# EasyEDApro.net
KiCad netlist of a schematic drawn in EasyEDA Pro
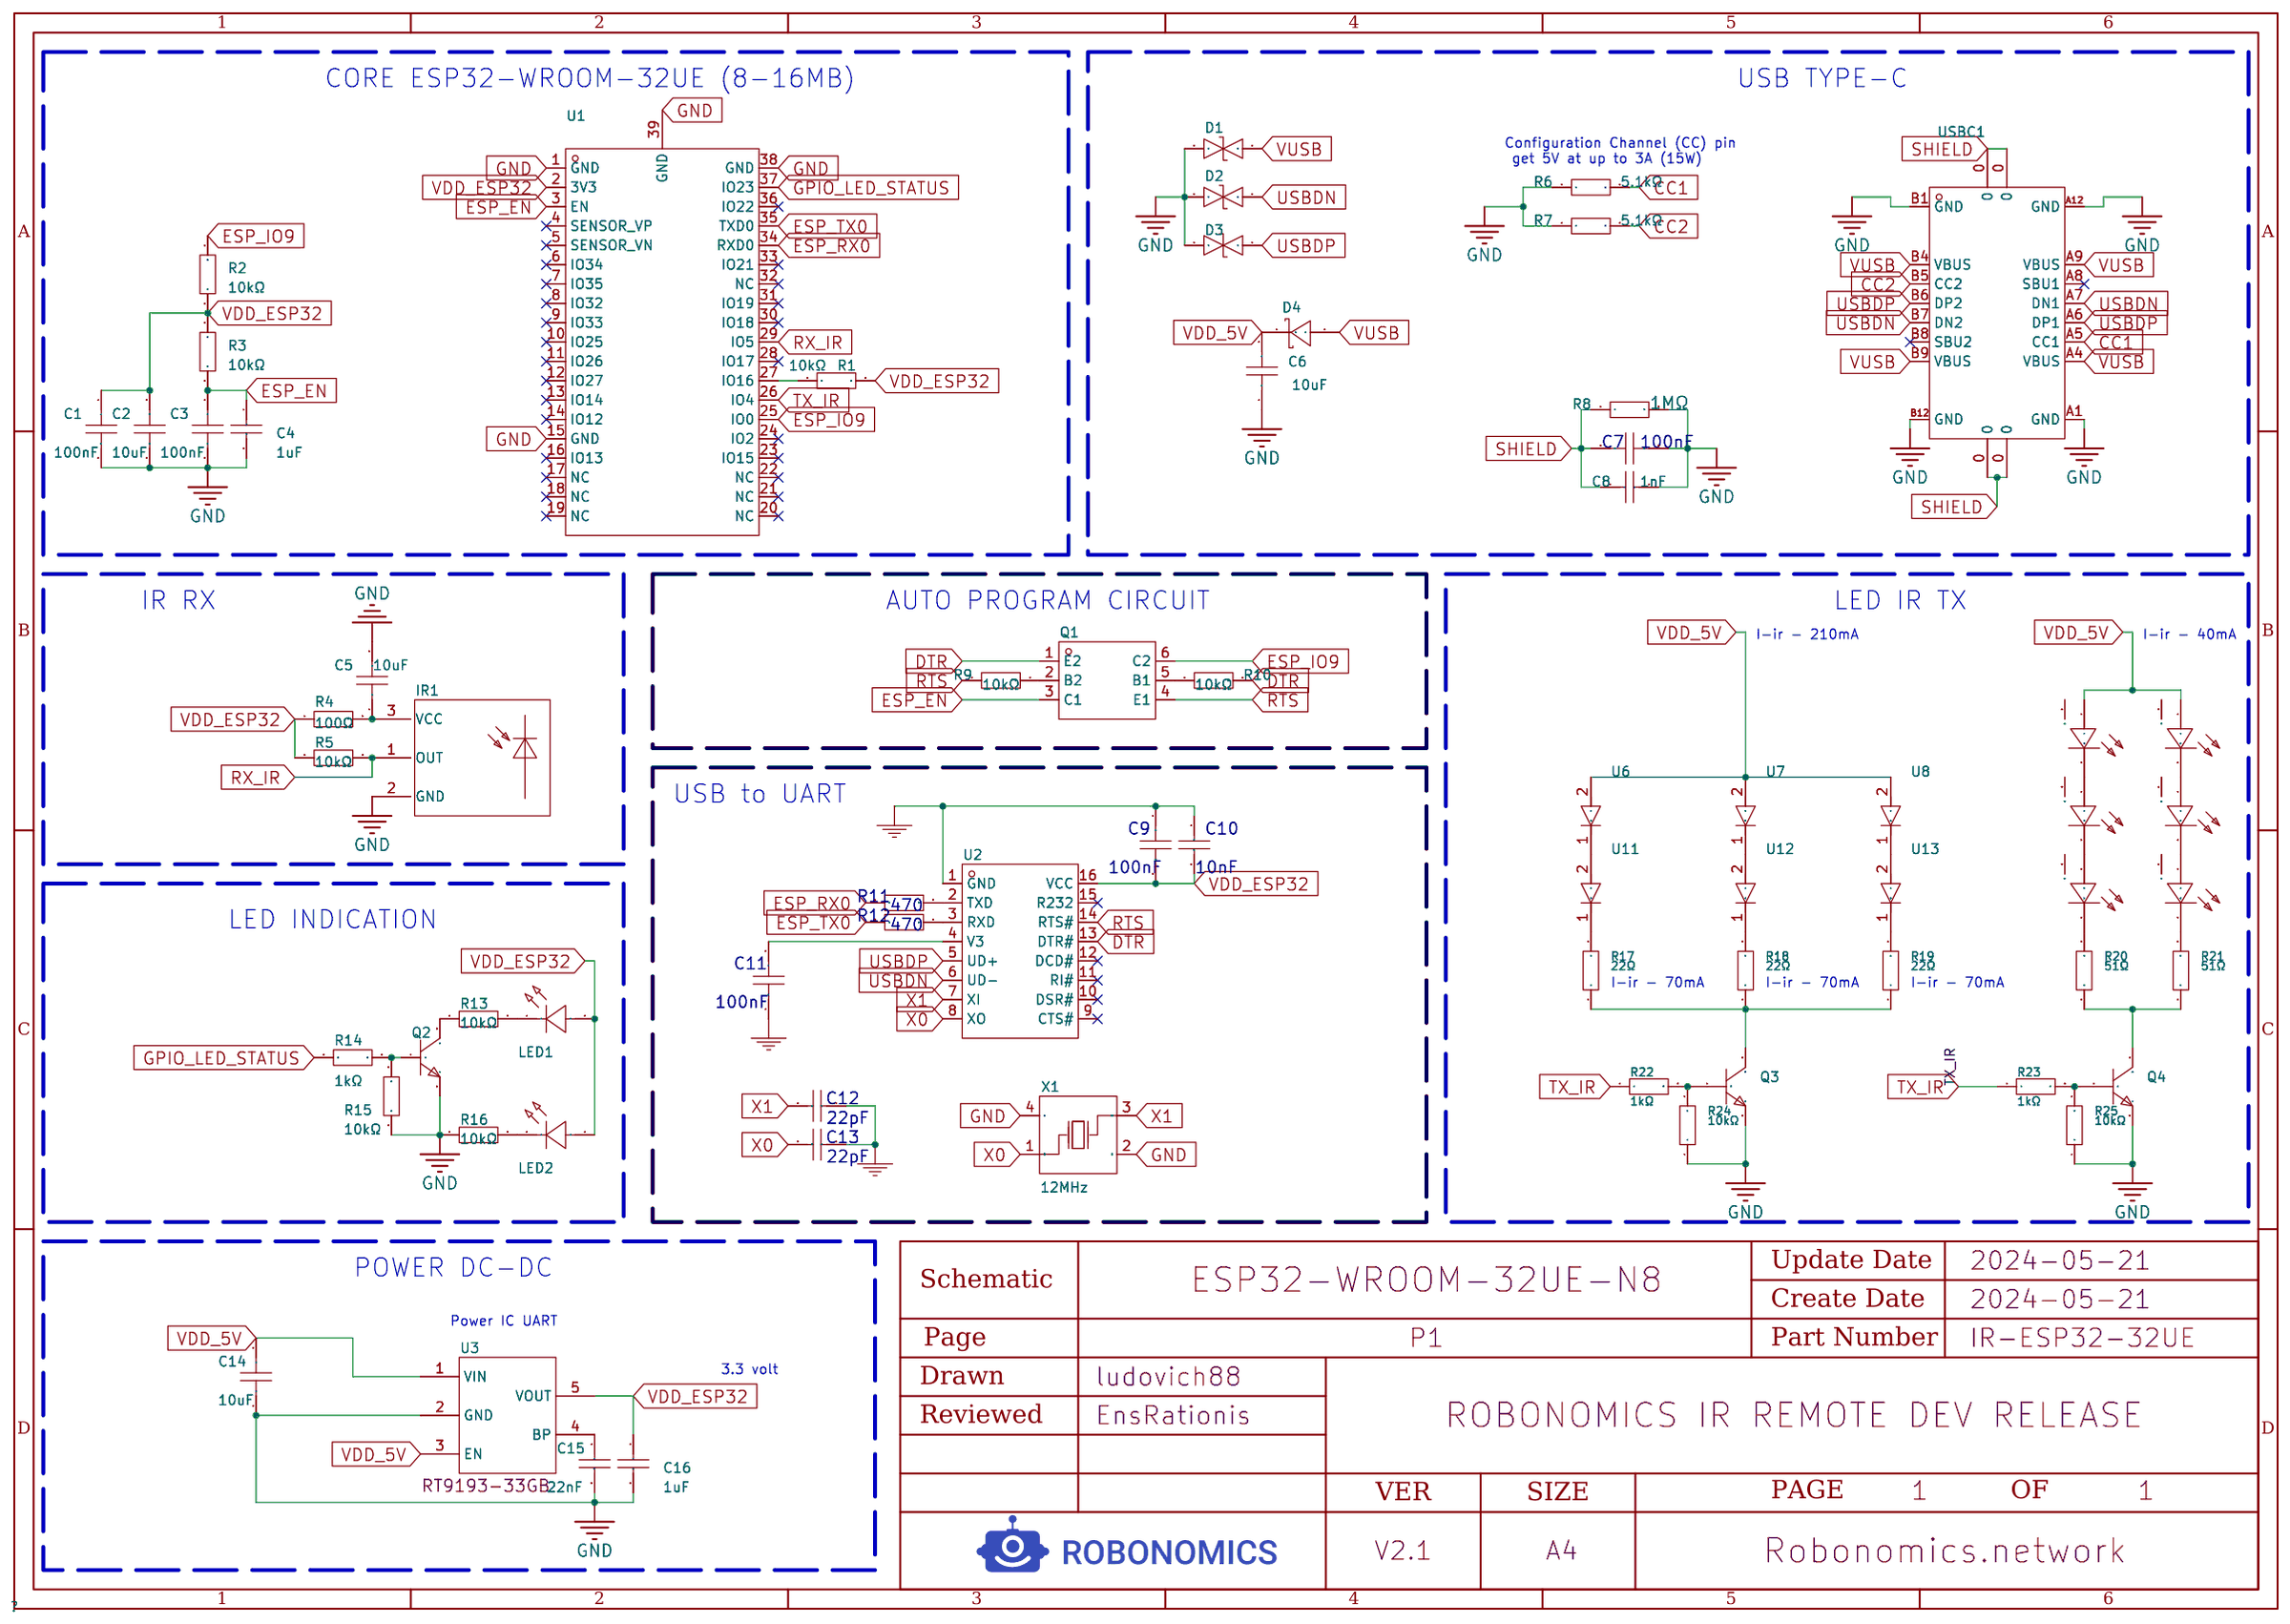
[diagram p0: schematic sheet]

(export (version "E")
  (design (tool "Eeschema 10.0.6"))
  (components
    (comp (ref "C1")
      (value "100nF")
      (fields
        (field (name "Manufacturer Part") "CC0603KRX7R9BB104")
        (field (name "Manufacturer") "YAGEO(国巨)")
      )
      (libsource (lib "easyedapro") (part "0603F104Z500"))
    )
    (comp (ref "C2")
      (value "10uF")
      (fields
        (field (name "Manufacturer Part") "CL10A106KP8NNNC")
        (field (name "Manufacturer") "SAMSUNG(三星)")
      )
      (libsource (lib "easyedapro") (part "CL10A106KP8NNNC"))
    )
    (comp (ref "C3")
      (value "100nF")
      (fields
        (field (name "Manufacturer Part") "CC0603KRX7R9BB104")
        (field (name "Manufacturer") "YAGEO(国巨)")
      )
      (libsource (lib "easyedapro") (part "0603F104Z500"))
    )
    (comp (ref "C4")
      (value "1uF")
      (footprint "easyedapro:C0603")
      (description "Capacitance:1uF Tolerance:±10% Tolerance:±10% Voltage Rated:50V Temperature Coefficient:X5R")
      (fields
        (field (name "Manufacturer Part") "CL10A105KB8NNNC")
        (field (name "Manufacturer") "SAMSUNG(三星)")
      )
      (libsource (lib "easyedapro") (part "CL10A105KB8NNNC"))
    )
    (comp (ref "C5")
      (value "10uF")
      (fields
        (field (name "Manufacturer Part") "CL10A106KP8NNNC")
        (field (name "Manufacturer") "SAMSUNG(三星)")
      )
      (libsource (lib "easyedapro") (part "CL10A106KP8NNNC"))
    )
    (comp (ref "C6")
      (value "10uF")
      (fields
        (field (name "Manufacturer Part") "CL10A106KP8NNNC")
        (field (name "Manufacturer") "SAMSUNG(三星)")
      )
      (libsource (lib "easyedapro") (part "CL10A106MA8NRNC"))
    )
    (comp (ref "C7")
      (value "100nF")
      (fields
        (field (name "Manufacturer Part") "CC0603KRX7R9BB104")
        (field (name "Manufacturer") "YAGEO(国巨)")
      )
      (libsource (lib "easyedapro") (part "100nF"))
    )
    (comp (ref "C8")
      (value "1nF")
      (footprint "easyedapro:C0603")
      (description "Capacitance:1nF Tolerance:±10% Tolerance:±10% Voltage Rated:50V Temperature Coefficient:X7R")
      (fields
        (field (name "Manufacturer Part") "CL10B102KB8NNNC")
        (field (name "Manufacturer") "SAMSUNG(三星)")
      )
      (libsource (lib "easyedapro") (part "CL10B102KB8NNNC"))
    )
    (comp (ref "C9")
      (value "100nF")
      (fields
        (field (name "Manufacturer Part") "CC0603KRX7R9BB104")
        (field (name "Manufacturer") "YAGEO(国巨)")
      )
      (libsource (lib "easyedapro") (part "100nF"))
    )
    (comp (ref "C10")
      (value "10nF")
      (footprint "easyedapro:C0603")
      (fields (field (name "Manufacturer Part") "0603B103K500NT") (field (name "Manufacturer") "FH"))
      (libsource (lib "easyedapro") (part "10nF"))
    )
    (comp (ref "C11")
      (value "100nF")
      (fields
        (field (name "Manufacturer Part") "CC0603KRX7R9BB104")
        (field (name "Manufacturer") "YAGEO(国巨)")
      )
      (libsource (lib "easyedapro") (part "100nF"))
    )
    (comp (ref "C12")
      (value "22pF")
      (footprint "easyedapro:C0603")
      (fields (field (name "Manufacturer Part") "CL10C220JB8NNNC") (field (name "Manufacturer") "SAMSUNG"))
      (libsource (lib "easyedapro") (part "22pF"))
    )
    (comp (ref "C13")
      (value "22pF")
      (footprint "easyedapro:C0603")
      (fields (field (name "Manufacturer Part") "CL10C220JB8NNNC") (field (name "Manufacturer") "SAMSUNG"))
      (libsource (lib "easyedapro") (part "22pF"))
    )
    (comp (ref "C14")
      (value "10uF")
      (fields
        (field (name "Manufacturer Part") "CL10A106KP8NNNC")
        (field (name "Manufacturer") "SAMSUNG(三星)")
      )
      (libsource (lib "easyedapro") (part "CL10A106KP8NNNC"))
    )
    (comp (ref "C15")
      (value "22nF")
      (footprint "easyedapro:C0603")
      (description "Capacitance:22nF Tolerance:±10% Tolerance:±10% Voltage Rated:50V Temperature Coefficient:X7R")
      (fields
        (field (name "Manufacturer Part") "CL10B223KB8NNNC")
        (field (name "Manufacturer") "SAMSUNG(三星)")
      )
      (libsource (lib "easyedapro") (part "CL10B223KB8NNNC"))
    )
    (comp (ref "C16")
      (value "1uF")
      (footprint "easyedapro:C0603")
      (description "Capacitance:1uF Tolerance:±10% Tolerance:±10% Voltage Rated:50V Temperature Coefficient:X5R")
      (fields
        (field (name "Manufacturer Part") "CL10A105KB8NNNC")
        (field (name "Manufacturer") "SAMSUNG(三星)")
      )
      (libsource (lib "easyedapro") (part "CL10A105KB8NNNC"))
    )
    (comp (ref "D1")
      (value "~")
      (footprint "easyedapro:SOD-523_L1.2-W0.8-LS1.6-BI")
      (fields (field (name "Manufacturer Part") "LESD5D5.0CT1G") (field (name "Manufacturer") "LRC(乐山无线电)"))
      (libsource (lib "easyedapro") (part "LESD5D5.0CT1G"))
    )
    (comp (ref "D2")
      (value "~")
      (footprint "easyedapro:SOD-523_L1.2-W0.8-LS1.6-BI")
      (fields (field (name "Manufacturer Part") "LESD5D5.0CT1G") (field (name "Manufacturer") "LRC(乐山无线电)"))
      (libsource (lib "easyedapro") (part "LESD5D5.0CT1G"))
    )
    (comp (ref "D3")
      (value "~")
      (footprint "easyedapro:SOD-523_L1.2-W0.8-LS1.6-BI")
      (fields (field (name "Manufacturer Part") "LESD5D5.0CT1G") (field (name "Manufacturer") "LRC(乐山无线电)"))
      (libsource (lib "easyedapro") (part "LESD5D5.0CT1G"))
    )
    (comp (ref "D4")
      (value "~")
      (footprint "easyedapro:SOD-123_L2.7-W1.6-LS3.7-RD")
      (description "Reverse Voltage (Vr):40V Average Rectified Current (Io):1A Forward Voltage (Vf@If):450mV@1A")
      (fields (field (name "Manufacturer Part") "1N5819HW-7-F") (field (name "Manufacturer") "DIODES(美台)"))
      (libsource (lib "easyedapro") (part "1N5819HW-7-F"))
    )
    (comp (ref "IR1")
      (value "~")
      (footprint "easyedapro:OPTO-TH_IRM-56384")
      (fields (field (name "Manufacturer Part") "IRM-56384") (field (name "Manufacturer") "EVERLIGHT(亿光)"))
      (libsource (lib "easyedapro") (part "IRM-56384"))
    )
    (comp (ref "LED1")
      (value "XL-4008UGC")
      (footprint "easyedapro:LED-SMD_L4.0-W1.4-RD_GREEN")
      (fields (field (name "Manufacturer") "XINGLIGHT(成兴光)"))
      (libsource (lib "easyedapro") (part "XL-4008UGC"))
    )
    (comp (ref "LED2")
      (value "XL-4008SURC")
      (footprint "easyedapro:LED-SMD_L4.0-W1.4-FD_C9900036310")
      (fields (field (name "Manufacturer") "XINGLIGHT(成兴光)"))
      (libsource (lib "easyedapro") (part "XL-4008SURC"))
    )
    (comp (ref "Q1")
      (value "~")
      (footprint "easyedapro:SOT-363_L2.0-W1.3-P0.65-LS2.1-BR")
      (fields (field (name "Manufacturer Part") "LBC847BDW1T1G") (field (name "Manufacturer") "LRC(乐山无线电)"))
      (libsource (lib "easyedapro") (part "LBC847BDW1T1G"))
    )
    (comp (ref "Q2")
      (value "SS8050")
      (footprint "easyedapro:SOT-23-3_L2.9-W1.6-P1.90-LS2.8-BR")
      (fields (field (name "Manufacturer") "Hottech(合科泰)"))
      (libsource (lib "easyedapro") (part "SS8050_C181160"))
    )
    (comp (ref "Q3")
      (value "~")
      (footprint "easyedapro:SOT-23-3_L2.9-W1.6-P1.90-LS2.8-BR")
      (fields (field (name "Manufacturer Part") "SS8050") (field (name "Manufacturer") "CJ(江苏长电/长晶)"))
      (libsource (lib "easyedapro") (part "SS8050_C177739"))
    )
    (comp (ref "Q4")
      (value "~")
      (footprint "easyedapro:SOT-23-3_L2.9-W1.6-P1.90-LS2.8-BR")
      (fields (field (name "Manufacturer Part") "SS8050") (field (name "Manufacturer") "CJ(江苏长电/长晶)"))
      (libsource (lib "easyedapro") (part "SS8050_C177739"))
    )
    (comp (ref "R1")
      (value "10kΩ")
      (fields
        (field (name "Manufacturer Part") "0603WAF1002T5E")
        (field (name "Manufacturer") "UNI-ROYAL(厚声)")
      )
      (libsource (lib "easyedapro") (part "0603WAF1002T5E"))
    )
    (comp (ref "R2")
      (value "10kΩ")
      (fields
        (field (name "Manufacturer Part") "0603WAF1002T5E")
        (field (name "Manufacturer") "UNI-ROYAL(厚声)")
      )
      (libsource (lib "easyedapro") (part "0603WAF1002T5E"))
    )
    (comp (ref "R3")
      (value "10kΩ")
      (fields
        (field (name "Manufacturer Part") "0603WAF1002T5E")
        (field (name "Manufacturer") "UNI-ROYAL(厚声)")
      )
      (libsource (lib "easyedapro") (part "0603WAF1002T5E"))
    )
    (comp (ref "R4")
      (value "100Ω")
      (footprint "easyedapro:R0603")
      (fields
        (field (name "Manufacturer Part") "0603WAF1000T5E")
        (field (name "Manufacturer") "UNI-ROYAL(厚声)")
      )
      (libsource (lib "easyedapro") (part "0603WAF1000T5E"))
    )
    (comp (ref "R5")
      (value "10kΩ")
      (fields
        (field (name "Manufacturer Part") "0603WAF1002T5E")
        (field (name "Manufacturer") "UNI-ROYAL(厚声)")
      )
      (libsource (lib "easyedapro") (part "0603WAF1002T5E"))
    )
    (comp (ref "R6")
      (value "5.1kΩ")
      (footprint "easyedapro:R0603")
      (fields
        (field (name "Manufacturer Part") "0603WAF5101T5E")
        (field (name "Manufacturer") "UNI-ROYAL(厚声)")
      )
      (libsource (lib "easyedapro") (part "0603WAF5101T5E"))
    )
    (comp (ref "R7")
      (value "5.1kΩ")
      (footprint "easyedapro:R0603")
      (fields
        (field (name "Manufacturer Part") "0603WAF5101T5E")
        (field (name "Manufacturer") "UNI-ROYAL(厚声)")
      )
      (libsource (lib "easyedapro") (part "0603WAF5101T5E"))
    )
    (comp (ref "R8")
      (value "1MΩ")
      (footprint "easyedapro:R0603")
      (fields
        (field (name "Manufacturer Part") "0603WAF1004T5E")
        (field (name "Manufacturer") "UNI-ROYAL(厚声)")
      )
      (libsource (lib "easyedapro") (part "0603WAF1004T5E"))
    )
    (comp (ref "R9")
      (value "10kΩ")
      (fields
        (field (name "Manufacturer Part") "0603WAF1002T5E")
        (field (name "Manufacturer") "UNI-ROYAL(厚声)")
      )
      (libsource (lib "easyedapro") (part "0603WAF1002T5E"))
    )
    (comp (ref "R10")
      (value "10kΩ")
      (fields
        (field (name "Manufacturer Part") "0603WAF1002T5E")
        (field (name "Manufacturer") "UNI-ROYAL(厚声)")
      )
      (libsource (lib "easyedapro") (part "0603WAF1002T5E"))
    )
    (comp (ref "R11")
      (value "470Ω")
      (footprint "easyedapro:R0603")
      (fields (field (name "Manufacturer Part") "0603WAF4700T5E") (field (name "Manufacturer") "UniOhm"))
      (libsource (lib "easyedapro") (part "470"))
    )
    (comp (ref "R12")
      (value "470Ω")
      (footprint "easyedapro:R0603")
      (fields (field (name "Manufacturer Part") "0603WAF4700T5E") (field (name "Manufacturer") "UniOhm"))
      (libsource (lib "easyedapro") (part "470"))
    )
    (comp (ref "R13")
      (value "10kΩ")
      (fields
        (field (name "Manufacturer Part") "0603WAF1002T5E")
        (field (name "Manufacturer") "UNI-ROYAL(厚声)")
      )
      (libsource (lib "easyedapro") (part "0603WAF1002T5E"))
    )
    (comp (ref "R14")
      (value "1kΩ")
      (footprint "easyedapro:R0603")
      (fields (field (name "Manufacturer Part") "RC0603FR-071KL") (field (name "Manufacturer") "YAGEO(国巨)"))
      (libsource (lib "easyedapro") (part "RC0603FR-071KL"))
    )
    (comp (ref "R15")
      (value "10kΩ")
      (fields
        (field (name "Manufacturer Part") "0603WAF1002T5E")
        (field (name "Manufacturer") "UNI-ROYAL(厚声)")
      )
      (libsource (lib "easyedapro") (part "0603WAF1002T5E"))
    )
    (comp (ref "R16")
      (value "10kΩ")
      (fields
        (field (name "Manufacturer Part") "0603WAF1002T5E")
        (field (name "Manufacturer") "UNI-ROYAL(厚声)")
      )
      (libsource (lib "easyedapro") (part "0603WAF1002T5E"))
    )
    (comp (ref "R17")
      (value "22Ω")
      (footprint "easyedapro:R0603")
      (fields
        (field (name "Manufacturer Part") "0603WAF220JT5E")
        (field (name "Manufacturer") "UNI-ROYAL(厚声)")
      )
      (libsource (lib "easyedapro") (part "0603WAF220JT5E"))
    )
    (comp (ref "R18")
      (value "22Ω")
      (footprint "easyedapro:R0603")
      (fields
        (field (name "Manufacturer Part") "0603WAF220JT5E")
        (field (name "Manufacturer") "UNI-ROYAL(厚声)")
      )
      (libsource (lib "easyedapro") (part "0603WAF220JT5E"))
    )
    (comp (ref "R19")
      (value "22Ω")
      (footprint "easyedapro:R0603")
      (fields
        (field (name "Manufacturer Part") "0603WAF220JT5E")
        (field (name "Manufacturer") "UNI-ROYAL(厚声)")
      )
      (libsource (lib "easyedapro") (part "0603WAF220JT5E"))
    )
    (comp (ref "R20")
      (value "51Ω")
      (footprint "easyedapro:R0603")
      (fields
        (field (name "Manufacturer Part") "0603WAF510JT5E")
        (field (name "Manufacturer") "UNI-ROYAL(厚声)")
      )
      (libsource (lib "easyedapro") (part "0603WAF510JT5E"))
    )
    (comp (ref "R21")
      (value "51Ω")
      (footprint "easyedapro:R0603")
      (fields
        (field (name "Manufacturer Part") "0603WAF510JT5E")
        (field (name "Manufacturer") "UNI-ROYAL(厚声)")
      )
      (libsource (lib "easyedapro") (part "0603WAF510JT5E"))
    )
    (comp (ref "R22")
      (value "1kΩ")
      (footprint "easyedapro:R0603")
      (fields
        (field (name "Manufacturer Part") "0603WAF1001T5E")
        (field (name "Manufacturer") "UNI-ROYAL(厚声)")
      )
      (libsource (lib "easyedapro") (part "0603WAF1001T5E"))
    )
    (comp (ref "R23")
      (value "1kΩ")
      (footprint "easyedapro:R0603")
      (fields
        (field (name "Manufacturer Part") "0603WAF1001T5E")
        (field (name "Manufacturer") "UNI-ROYAL(厚声)")
      )
      (libsource (lib "easyedapro") (part "0603WAF1001T5E"))
    )
    (comp (ref "R24")
      (value "10kΩ")
      (footprint "easyedapro:R0603")
      (fields
        (field (name "Manufacturer Part") "0603WAF1002T5E")
        (field (name "Manufacturer") "UNI-ROYAL(厚声)")
      )
      (libsource (lib "easyedapro") (part "0603WAF1002T5E"))
    )
    (comp (ref "R25")
      (value "10kΩ")
      (footprint "easyedapro:R0603")
      (fields
        (field (name "Manufacturer Part") "0603WAF1002T5E")
        (field (name "Manufacturer") "UNI-ROYAL(厚声)")
      )
      (libsource (lib "easyedapro") (part "0603WAF1002T5E"))
    )
    (comp (ref "U1")
      (value "~")
      (footprint "easyedapro:WIFI-SMD_ESP32-WROOM-32UE")
      (fields
        (field (name "Manufacturer Part") "ESP32-WROOM-32UE-N8")
        (field (name "Manufacturer") "ESPRESSIF(乐鑫)")
      )
      (libsource (lib "easyedapro") (part "ESP32-WROOM-32UE(8MB)"))
    )
    (comp (ref "U2")
      (value "~")
      (footprint "easyedapro:SOIC-16_L9.9-W3.9-P1.27-LS6.0-BL")
      (fields (field (name "Manufacturer Part") "CH340G") (field (name "Manufacturer") "WCH(南京沁恒)"))
      (libsource (lib "easyedapro") (part "CH340G"))
    )
    (comp (ref "U3")
      (value "~")
      (footprint "easyedapro:SOT-23-5_L3.0-W1.7-P0.95-LS2.8-BR")
      (fields (field (name "Manufacturer Part") "RT9193-33GB") (field (name "Manufacturer") "RICHTEK(台湾立锜)"))
      (libsource (lib "easyedapro") (part "RT9193-33GB"))
    )
    (comp (ref "U4")
      (value "LKIR30102C-A01(XY)")
      (footprint "easyedapro:LED-SMD_EVERLIGHT_LKIR30102C-A01XY")
      (fields (field (name "Manufacturer") "EVERLIGHT(亿光)"))
      (libsource (lib "easyedapro") (part "LKIR30102C-A01(XY)"))
    )
    (comp (ref "U5")
      (value "LKIR30102C-A01(XY)")
      (footprint "easyedapro:LED-SMD_EVERLIGHT_LKIR30102C-A01XY")
      (fields (field (name "Manufacturer") "EVERLIGHT(亿光)"))
      (libsource (lib "easyedapro") (part "LKIR30102C-A01(XY)"))
    )
    (comp (ref "U6")
      (value "SFH 4253-Z")
      (footprint "easyedapro:OPTO-SMD_L3.2-W2.8-LS3.5-L-1")
      (fields (field (name "Manufacturer") "OSRAM(欧司朗)"))
      (libsource (lib "easyedapro") (part "SFH 4253-Z"))
    )
    (comp (ref "U7")
      (value "SFH 4253-Z")
      (footprint "easyedapro:OPTO-SMD_L3.2-W2.8-LS3.5-L-1")
      (fields (field (name "Manufacturer") "OSRAM(欧司朗)"))
      (libsource (lib "easyedapro") (part "SFH 4253-Z"))
    )
    (comp (ref "U8")
      (value "SFH 4253-Z")
      (footprint "easyedapro:OPTO-SMD_L3.2-W2.8-LS3.5-L-1")
      (fields (field (name "Manufacturer") "OSRAM(欧司朗)"))
      (libsource (lib "easyedapro") (part "SFH 4253-Z"))
    )
    (comp (ref "U9")
      (value "LKIR30102C-A01(XY)")
      (footprint "easyedapro:LED-SMD_EVERLIGHT_LKIR30102C-A01XY")
      (fields (field (name "Manufacturer") "EVERLIGHT(亿光)"))
      (libsource (lib "easyedapro") (part "LKIR30102C-A01(XY)"))
    )
    (comp (ref "U10")
      (value "LKIR30102C-A01(XY)")
      (footprint "easyedapro:LED-SMD_EVERLIGHT_LKIR30102C-A01XY")
      (fields (field (name "Manufacturer") "EVERLIGHT(亿光)"))
      (libsource (lib "easyedapro") (part "LKIR30102C-A01(XY)"))
    )
    (comp (ref "U11")
      (value "SFH 4253-Z")
      (footprint "easyedapro:OPTO-SMD_L3.2-W2.8-LS3.5-L-1")
      (fields (field (name "Manufacturer") "OSRAM(欧司朗)"))
      (libsource (lib "easyedapro") (part "SFH 4253-Z"))
    )
    (comp (ref "U12")
      (value "SFH 4253-Z")
      (footprint "easyedapro:OPTO-SMD_L3.2-W2.8-LS3.5-L-1")
      (fields (field (name "Manufacturer") "OSRAM(欧司朗)"))
      (libsource (lib "easyedapro") (part "SFH 4253-Z"))
    )
    (comp (ref "U13")
      (value "SFH 4253-Z")
      (footprint "easyedapro:OPTO-SMD_L3.2-W2.8-LS3.5-L-1")
      (fields (field (name "Manufacturer") "OSRAM(欧司朗)"))
      (libsource (lib "easyedapro") (part "SFH 4253-Z"))
    )
    (comp (ref "U14")
      (value "LKIR30102C-A01(XY)")
      (footprint "easyedapro:LED-SMD_EVERLIGHT_LKIR30102C-A01XY")
      (fields (field (name "Manufacturer") "EVERLIGHT(亿光)"))
      (libsource (lib "easyedapro") (part "LKIR30102C-A01(XY)"))
    )
    (comp (ref "U15")
      (value "LKIR30102C-A01(XY)")
      (footprint "easyedapro:LED-SMD_EVERLIGHT_LKIR30102C-A01XY")
      (fields (field (name "Manufacturer") "EVERLIGHT(亿光)"))
      (libsource (lib "easyedapro") (part "LKIR30102C-A01(XY)"))
    )
    (comp (ref "USBC1")
      (value "~")
      (footprint "easyedapro:USB-C_SMD-TYPE-C-31-M-12")
      (fields (field (name "Manufacturer Part") "TYPE-C-31-M-12") (field (name "Manufacturer") "韩国韩荣"))
      (libsource (lib "easyedapro") (part "TYPE-C-31-M-12"))
    )
    (comp (ref "X1")
      (value "12MHz")
      (footprint "easyedapro:OSC-SMD_4P-L3.2-W2.5-BL")
      (fields (field (name "Manufacturer Part") "X322512MSB4SI") (field (name "Manufacturer") "YXC扬兴科技"))
      (libsource (lib "easyedapro") (part "X322512MSB4SI"))
    )
  )
  (nets
    (net (code "1") (name "CC1") (class "Default")
      (node (ref "R6") (pin "2") (pinfunction "2_2") (pintype "input"))
      (node (ref "USBC1") (pin "A5") (pinfunction "CC1_A5") (pintype "input"))
    )
    (net (code "2") (name "CC2") (class "Default")
      (node (ref "R7") (pin "2") (pinfunction "2_2") (pintype "input"))
      (node (ref "USBC1") (pin "B5") (pinfunction "CC2_B5") (pintype "input"))
    )
    (net (code "3") (name "DTR") (class "Default")
      (node (ref "Q1") (pin "1") (pinfunction "E2_1") (pintype "input"))
      (node (ref "R10") (pin "2") (pinfunction "2_2") (pintype "input"))
      (node (ref "U2") (pin "13") (pinfunction "DTR#_13") (pintype "input"))
    )
    (net (code "4") (name "ESP_EN") (class "Default")
      (node (ref "C3") (pin "1") (pinfunction "1_1") (pintype "input"))
      (node (ref "C4") (pin "1") (pinfunction "1_1") (pintype "input"))
      (node (ref "Q1") (pin "3") (pinfunction "C1_3") (pintype "input"))
      (node (ref "R3") (pin "2") (pinfunction "2_2") (pintype "input"))
      (node (ref "U1") (pin "3") (pinfunction "EN_3") (pintype "input"))
    )
    (net (code "5") (name "ESP_IO9") (class "Default")
      (node (ref "Q1") (pin "6") (pinfunction "C2_6") (pintype "input"))
      (node (ref "R2") (pin "1") (pinfunction "1_1") (pintype "input"))
      (node (ref "U1") (pin "25") (pinfunction "IO0_25") (pintype "input"))
    )
    (net (code "6") (name "ESP_RX0") (class "Default")
      (node (ref "R11") (pin "1") (pinfunction "1_1") (pintype "input"))
      (node (ref "U1") (pin "34") (pinfunction "RXD0_34") (pintype "input"))
    )
    (net (code "7") (name "ESP_TX0") (class "Default")
      (node (ref "R12") (pin "1") (pinfunction "1_1") (pintype "input"))
      (node (ref "U1") (pin "35") (pinfunction "TXD0_35") (pintype "input"))
    )
    (net (code "8") (name "GND") (class "Default")
      (node (ref "C1") (pin "2") (pinfunction "2_2") (pintype "input"))
      (node (ref "C10") (pin "1") (pinfunction "1_1") (pintype "input"))
      (node (ref "C11") (pin "1") (pinfunction "1_1") (pintype "input"))
      (node (ref "C12") (pin "1") (pinfunction "1_1") (pintype "input"))
      (node (ref "C13") (pin "1") (pinfunction "1_1") (pintype "input"))
      (node (ref "C14") (pin "1") (pinfunction "1_1") (pintype "input"))
      (node (ref "C15") (pin "2") (pinfunction "2_2") (pintype "input"))
      (node (ref "C16") (pin "2") (pinfunction "2_2") (pintype "input"))
      (node (ref "C2") (pin "1") (pinfunction "1_1") (pintype "input"))
      (node (ref "C3") (pin "2") (pinfunction "2_2") (pintype "input"))
      (node (ref "C4") (pin "2") (pinfunction "2_2") (pintype "input"))
      (node (ref "C5") (pin "2") (pinfunction "2_2") (pintype "input"))
      (node (ref "C6") (pin "1") (pinfunction "1_1") (pintype "input"))
      (node (ref "C7") (pin "1") (pinfunction "1_1") (pintype "input"))
      (node (ref "C8") (pin "2") (pinfunction "2_2") (pintype "input"))
      (node (ref "C9") (pin "1") (pinfunction "1_1") (pintype "input"))
      (node (ref "D1") (pin "2") (pinfunction "2_2") (pintype "input"))
      (node (ref "D2") (pin "2") (pinfunction "2_2") (pintype "input"))
      (node (ref "D3") (pin "2") (pinfunction "2_2") (pintype "input"))
      (node (ref "IR1") (pin "2") (pinfunction "GND_2") (pintype "input"))
      (node (ref "Q2") (pin "2") (pinfunction "E_2") (pintype "input"))
      (node (ref "Q3") (pin "2") (pinfunction "E_2") (pintype "input"))
      (node (ref "Q4") (pin "2") (pinfunction "E_2") (pintype "input"))
      (node (ref "R15") (pin "1") (pinfunction "1_1") (pintype "input"))
      (node (ref "R16") (pin "1") (pinfunction "1_1") (pintype "input"))
      (node (ref "R24") (pin "1") (pinfunction "1_1") (pintype "input"))
      (node (ref "R25") (pin "1") (pinfunction "1_1") (pintype "input"))
      (node (ref "R6") (pin "1") (pinfunction "1_1") (pintype "input"))
      (node (ref "R7") (pin "1") (pinfunction "1_1") (pintype "input"))
      (node (ref "R8") (pin "2") (pinfunction "2_2") (pintype "input"))
      (node (ref "U1") (pin "1") (pinfunction "GND_1") (pintype "input"))
      (node (ref "U1") (pin "15") (pinfunction "GND_15") (pintype "input"))
      (node (ref "U1") (pin "38") (pinfunction "GND_38") (pintype "input"))
      (node (ref "U1") (pin "39") (pinfunction "GND_39") (pintype "input"))
      (node (ref "U2") (pin "1") (pinfunction "GND_1") (pintype "input"))
      (node (ref "U3") (pin "2") (pinfunction "GND_2") (pintype "input"))
      (node (ref "USBC1") (pin "A1") (pinfunction "GND_A1") (pintype "input"))
      (node (ref "USBC1") (pin "A12") (pinfunction "GND_A12") (pintype "input"))
      (node (ref "USBC1") (pin "B1") (pinfunction "GND_B1") (pintype "input"))
      (node (ref "USBC1") (pin "B12") (pinfunction "GND_B12") (pintype "input"))
      (node (ref "X1") (pin "2") (pinfunction "GND_2") (pintype "input"))
      (node (ref "X1") (pin "4") (pinfunction "GND_4") (pintype "input"))
    )
    (net (code "9") (name "GPIO_LED_STATUS") (class "Default")
      (node (ref "R14") (pin "1") (pinfunction "1_1") (pintype "input"))
      (node (ref "U1") (pin "37") (pinfunction "IO23_37") (pintype "input"))
    )
    (net (code "10") (name "Net-(IR1-VCC)") (class "Default")
      (node (ref "C5") (pin "1") (pinfunction "1_1") (pintype "input"))
      (node (ref "IR1") (pin "3") (pinfunction "VCC_3") (pintype "input"))
      (node (ref "R4") (pin "2") (pinfunction "2_2") (pintype "input"))
    )
    (net (code "11") (name "Net-(LED1-K)") (class "Default")
      (node (ref "LED1") (pin "1") (pinfunction "K_1") (pintype "input"))
      (node (ref "R13") (pin "2") (pinfunction "2_2") (pintype "input"))
    )
    (net (code "12") (name "Net-(LED2-K)") (class "Default")
      (node (ref "LED2") (pin "2") (pinfunction "K_2") (pintype "input"))
      (node (ref "R16") (pin "2") (pinfunction "2_2") (pintype "input"))
    )
    (net (code "13") (name "Net-(Q1-B1)") (class "Default")
      (node (ref "Q1") (pin "5") (pinfunction "B1_5") (pintype "input"))
      (node (ref "R10") (pin "1") (pinfunction "1_1") (pintype "input"))
    )
    (net (code "14") (name "Net-(Q1-B2)") (class "Default")
      (node (ref "Q1") (pin "2") (pinfunction "B2_2") (pintype "input"))
      (node (ref "R9") (pin "2") (pinfunction "2_2") (pintype "input"))
    )
    (net (code "15") (name "Net-(Q2-B)") (class "Default")
      (node (ref "Q2") (pin "1") (pinfunction "B_1") (pintype "input"))
      (node (ref "R14") (pin "2") (pinfunction "2_2") (pintype "input"))
      (node (ref "R15") (pin "2") (pinfunction "2_2") (pintype "input"))
    )
    (net (code "16") (name "Net-(Q2-C)") (class "Default")
      (node (ref "Q2") (pin "3") (pinfunction "C_3") (pintype "input"))
      (node (ref "R13") (pin "1") (pinfunction "1_1") (pintype "input"))
    )
    (net (code "17") (name "Net-(Q3-B)") (class "Default")
      (node (ref "Q3") (pin "1") (pinfunction "B_1") (pintype "input"))
      (node (ref "R22") (pin "2") (pinfunction "2_2") (pintype "input"))
      (node (ref "R24") (pin "2") (pinfunction "2_2") (pintype "input"))
    )
    (net (code "18") (name "Net-(Q3-C)") (class "Default")
      (node (ref "Q3") (pin "3") (pinfunction "C_3") (pintype "input"))
      (node (ref "R17") (pin "1") (pinfunction "1_1") (pintype "input"))
      (node (ref "R18") (pin "1") (pinfunction "1_1") (pintype "input"))
      (node (ref "R19") (pin "1") (pinfunction "1_1") (pintype "input"))
    )
    (net (code "19") (name "Net-(Q4-B)") (class "Default")
      (node (ref "Q4") (pin "1") (pinfunction "B_1") (pintype "input"))
      (node (ref "R23") (pin "2") (pinfunction "2_2") (pintype "input"))
      (node (ref "R25") (pin "2") (pinfunction "2_2") (pintype "input"))
    )
    (net (code "20") (name "Net-(Q4-C)") (class "Default")
      (node (ref "Q4") (pin "3") (pinfunction "C_3") (pintype "input"))
      (node (ref "R20") (pin "1") (pinfunction "1_1") (pintype "input"))
      (node (ref "R21") (pin "1") (pinfunction "1_1") (pintype "input"))
    )
    (net (code "21") (name "Net-(U1-IO16)") (class "Default")
      (node (ref "R1") (pin "1") (pinfunction "1_1") (pintype "input"))
      (node (ref "U1") (pin "27") (pinfunction "IO16_27") (pintype "input"))
    )
    (net (code "22") (name "Net-(U2-RXD)") (class "Default")
      (node (ref "R12") (pin "2") (pinfunction "2_2") (pintype "input"))
      (node (ref "U2") (pin "3") (pinfunction "RXD_3") (pintype "input"))
    )
    (net (code "23") (name "Net-(U2-TXD)") (class "Default")
      (node (ref "R11") (pin "2") (pinfunction "2_2") (pintype "input"))
      (node (ref "U2") (pin "2") (pinfunction "TXD_2") (pintype "input"))
    )
    (net (code "24") (name "Net-(U2-V3)") (class "Default")
      (node (ref "C11") (pin "2") (pinfunction "2_2") (pintype "input"))
      (node (ref "U2") (pin "4") (pinfunction "V3_4") (pintype "input"))
    )
    (net (code "25") (name "Net-(U3-BP)") (class "Default")
      (node (ref "C15") (pin "1") (pinfunction "1_1") (pintype "input"))
      (node (ref "U3") (pin "4") (pinfunction "BP_4") (pintype "input"))
    )
    (net (code "26") (name "Net-(U4-C)") (class "Default")
      (node (ref "U4") (pin "2") (pinfunction "C_2") (pintype "input"))
      (node (ref "U9") (pin "1") (pinfunction "A_1") (pintype "input"))
    )
    (net (code "27") (name "Net-(U10-A)") (class "Default")
      (node (ref "U10") (pin "1") (pinfunction "A_1") (pintype "input"))
      (node (ref "U5") (pin "2") (pinfunction "C_2") (pintype "input"))
    )
    (net (code "28") (name "Net-(U10-C)") (class "Default")
      (node (ref "U10") (pin "2") (pinfunction "C_2") (pintype "input"))
      (node (ref "U15") (pin "1") (pinfunction "A_1") (pintype "input"))
    )
    (net (code "29") (name "Net-(U11-A)") (class "Default")
      (node (ref "U11") (pin "2") (pinfunction "A_2") (pintype "input"))
      (node (ref "U6") (pin "1") (pinfunction "C_1") (pintype "input"))
    )
    (net (code "30") (name "Net-(U11-C)") (class "Default")
      (node (ref "R17") (pin "2") (pinfunction "2_2") (pintype "input"))
      (node (ref "U11") (pin "1") (pinfunction "C_1") (pintype "input"))
    )
    (net (code "31") (name "Net-(U12-A)") (class "Default")
      (node (ref "U12") (pin "2") (pinfunction "A_2") (pintype "input"))
      (node (ref "U7") (pin "1") (pinfunction "C_1") (pintype "input"))
    )
    (net (code "32") (name "Net-(U12-C)") (class "Default")
      (node (ref "R18") (pin "2") (pinfunction "2_2") (pintype "input"))
      (node (ref "U12") (pin "1") (pinfunction "C_1") (pintype "input"))
    )
    (net (code "33") (name "Net-(U13-A)") (class "Default")
      (node (ref "U13") (pin "2") (pinfunction "A_2") (pintype "input"))
      (node (ref "U8") (pin "1") (pinfunction "C_1") (pintype "input"))
    )
    (net (code "34") (name "Net-(U13-C)") (class "Default")
      (node (ref "R19") (pin "2") (pinfunction "2_2") (pintype "input"))
      (node (ref "U13") (pin "1") (pinfunction "C_1") (pintype "input"))
    )
    (net (code "35") (name "Net-(U14-A)") (class "Default")
      (node (ref "U14") (pin "1") (pinfunction "A_1") (pintype "input"))
      (node (ref "U9") (pin "2") (pinfunction "C_2") (pintype "input"))
    )
    (net (code "36") (name "Net-(U14-C)") (class "Default")
      (node (ref "R20") (pin "2") (pinfunction "2_2") (pintype "input"))
      (node (ref "U14") (pin "2") (pinfunction "C_2") (pintype "input"))
    )
    (net (code "37") (name "Net-(U15-C)") (class "Default")
      (node (ref "R21") (pin "2") (pinfunction "2_2") (pintype "input"))
      (node (ref "U15") (pin "2") (pinfunction "C_2") (pintype "input"))
    )
    (net (code "38") (name "RTS") (class "Default")
      (node (ref "Q1") (pin "4") (pinfunction "E1_4") (pintype "input"))
      (node (ref "R9") (pin "1") (pinfunction "1_1") (pintype "input"))
      (node (ref "U2") (pin "14") (pinfunction "RTS#_14") (pintype "input"))
    )
    (net (code "39") (name "RX_IR") (class "Default")
      (node (ref "IR1") (pin "1") (pinfunction "OUT_1") (pintype "input"))
      (node (ref "R5") (pin "2") (pinfunction "2_2") (pintype "input"))
      (node (ref "U1") (pin "29") (pinfunction "IO5_29") (pintype "input"))
    )
    (net (code "40") (name "SHIELD") (class "Default")
      (node (ref "C7") (pin "2") (pinfunction "2_2") (pintype "input"))
      (node (ref "C8") (pin "1") (pinfunction "1_1") (pintype "input"))
      (node (ref "R8") (pin "1") (pinfunction "1_1") (pintype "input"))
      (node (ref "USBC1") (pin "0") (pinfunction "0_0") (pintype "input"))
    )
    (net (code "41") (name "TX_IR") (class "Default")
      (node (ref "R22") (pin "1") (pinfunction "1_1") (pintype "input"))
      (node (ref "R23") (pin "1") (pinfunction "1_1") (pintype "input"))
      (node (ref "U1") (pin "26") (pinfunction "IO4_26") (pintype "input"))
    )
    (net (code "42") (name "USBDN") (class "Default")
      (node (ref "D2") (pin "1") (pinfunction "1_1") (pintype "input"))
      (node (ref "U2") (pin "6") (pinfunction "UD-_6") (pintype "input"))
      (node (ref "USBC1") (pin "A7") (pinfunction "DN1_A7") (pintype "input"))
      (node (ref "USBC1") (pin "B7") (pinfunction "DN2_B7") (pintype "input"))
    )
    (net (code "43") (name "USBDP") (class "Default")
      (node (ref "D3") (pin "1") (pinfunction "1_1") (pintype "input"))
      (node (ref "U2") (pin "5") (pinfunction "UD+_5") (pintype "input"))
      (node (ref "USBC1") (pin "A6") (pinfunction "DP1_A6") (pintype "input"))
      (node (ref "USBC1") (pin "B6") (pinfunction "DP2_B6") (pintype "input"))
    )
    (net (code "44") (name "VDD_5V") (class "Default")
      (node (ref "C14") (pin "2") (pinfunction "2_2") (pintype "input"))
      (node (ref "C6") (pin "2") (pinfunction "2_2") (pintype "input"))
      (node (ref "D4") (pin "1") (pinfunction "K_1") (pintype "input"))
      (node (ref "U3") (pin "1") (pinfunction "VIN_1") (pintype "input"))
      (node (ref "U3") (pin "3") (pinfunction "EN_3") (pintype "input"))
      (node (ref "U4") (pin "1") (pinfunction "A_1") (pintype "input"))
      (node (ref "U5") (pin "1") (pinfunction "A_1") (pintype "input"))
      (node (ref "U6") (pin "2") (pinfunction "A_2") (pintype "input"))
      (node (ref "U7") (pin "2") (pinfunction "A_2") (pintype "input"))
      (node (ref "U8") (pin "2") (pinfunction "A_2") (pintype "input"))
    )
    (net (code "45") (name "VDD_ESP32") (class "Default")
      (node (ref "C1") (pin "1") (pinfunction "1_1") (pintype "input"))
      (node (ref "C10") (pin "2") (pinfunction "2_2") (pintype "input"))
      (node (ref "C16") (pin "1") (pinfunction "1_1") (pintype "input"))
      (node (ref "C2") (pin "2") (pinfunction "2_2") (pintype "input"))
      (node (ref "C9") (pin "2") (pinfunction "2_2") (pintype "input"))
      (node (ref "LED1") (pin "2") (pinfunction "A_2") (pintype "input"))
      (node (ref "LED2") (pin "1") (pinfunction "A_1") (pintype "input"))
      (node (ref "R1") (pin "2") (pinfunction "2_2") (pintype "input"))
      (node (ref "R2") (pin "2") (pinfunction "2_2") (pintype "input"))
      (node (ref "R3") (pin "1") (pinfunction "1_1") (pintype "input"))
      (node (ref "R4") (pin "1") (pinfunction "1_1") (pintype "input"))
      (node (ref "R5") (pin "1") (pinfunction "1_1") (pintype "input"))
      (node (ref "U1") (pin "2") (pinfunction "3V3_2") (pintype "input"))
      (node (ref "U2") (pin "16") (pinfunction "VCC_16") (pintype "input"))
      (node (ref "U3") (pin "5") (pinfunction "VOUT_5") (pintype "input"))
    )
    (net (code "46") (name "VUSB") (class "Default")
      (node (ref "D1") (pin "1") (pinfunction "1_1") (pintype "input"))
      (node (ref "D4") (pin "2") (pinfunction "A_2") (pintype "input"))
      (node (ref "USBC1") (pin "A4") (pinfunction "VBUS_A4") (pintype "input"))
      (node (ref "USBC1") (pin "A9") (pinfunction "VBUS_A9") (pintype "input"))
      (node (ref "USBC1") (pin "B4") (pinfunction "VBUS_B4") (pintype "input"))
      (node (ref "USBC1") (pin "B9") (pinfunction "VBUS_B9") (pintype "input"))
    )
    (net (code "47") (name "X0") (class "Default")
      (node (ref "C13") (pin "2") (pinfunction "2_2") (pintype "input"))
      (node (ref "U2") (pin "8") (pinfunction "XO_8") (pintype "input"))
      (node (ref "X1") (pin "1") (pinfunction "OSC1_1") (pintype "input"))
    )
    (net (code "48") (name "X1") (class "Default")
      (node (ref "C12") (pin "2") (pinfunction "2_2") (pintype "input"))
      (node (ref "U2") (pin "7") (pinfunction "XI_7") (pintype "input"))
      (node (ref "X1") (pin "3") (pinfunction "OSC2_3") (pintype "input"))
    )
    (net (code "49") (name "unconnected-(U1-IO2-Pad24)") (class "Default")
      (node (ref "U1") (pin "24") (pinfunction "IO2_24") (pintype "input+no_connect"))
    )
    (net (code "50") (name "unconnected-(U1-IO12-Pad14)") (class "Default")
      (node (ref "U1") (pin "14") (pinfunction "IO12_14") (pintype "input+no_connect"))
    )
    (net (code "51") (name "unconnected-(U1-IO13-Pad16)") (class "Default")
      (node (ref "U1") (pin "16") (pinfunction "IO13_16") (pintype "input+no_connect"))
    )
    (net (code "52") (name "unconnected-(U1-IO14-Pad13)") (class "Default")
      (node (ref "U1") (pin "13") (pinfunction "IO14_13") (pintype "input+no_connect"))
    )
    (net (code "53") (name "unconnected-(U1-IO15-Pad23)") (class "Default")
      (node (ref "U1") (pin "23") (pinfunction "IO15_23") (pintype "input+no_connect"))
    )
    (net (code "54") (name "unconnected-(U1-IO17-Pad28)") (class "Default")
      (node (ref "U1") (pin "28") (pinfunction "IO17_28") (pintype "input+no_connect"))
    )
    (net (code "55") (name "unconnected-(U1-IO18-Pad30)") (class "Default")
      (node (ref "U1") (pin "30") (pinfunction "IO18_30") (pintype "input+no_connect"))
    )
    (net (code "56") (name "unconnected-(U1-IO19-Pad31)") (class "Default")
      (node (ref "U1") (pin "31") (pinfunction "IO19_31") (pintype "input+no_connect"))
    )
    (net (code "57") (name "unconnected-(U1-IO21-Pad33)") (class "Default")
      (node (ref "U1") (pin "33") (pinfunction "IO21_33") (pintype "input+no_connect"))
    )
    (net (code "58") (name "unconnected-(U1-IO22-Pad36)") (class "Default")
      (node (ref "U1") (pin "36") (pinfunction "IO22_36") (pintype "input+no_connect"))
    )
    (net (code "59") (name "unconnected-(U1-IO25-Pad10)") (class "Default")
      (node (ref "U1") (pin "10") (pinfunction "IO25_10") (pintype "input+no_connect"))
    )
    (net (code "60") (name "unconnected-(U1-IO26-Pad11)") (class "Default")
      (node (ref "U1") (pin "11") (pinfunction "IO26_11") (pintype "input+no_connect"))
    )
    (net (code "61") (name "unconnected-(U1-IO27-Pad12)") (class "Default")
      (node (ref "U1") (pin "12") (pinfunction "IO27_12") (pintype "input+no_connect"))
    )
    (net (code "62") (name "unconnected-(U1-IO32-Pad8)") (class "Default")
      (node (ref "U1") (pin "8") (pinfunction "IO32_8") (pintype "input+no_connect"))
    )
    (net (code "63") (name "unconnected-(U1-IO33-Pad9)") (class "Default")
      (node (ref "U1") (pin "9") (pinfunction "IO33_9") (pintype "input+no_connect"))
    )
    (net (code "64") (name "unconnected-(U1-IO34-Pad6)") (class "Default")
      (node (ref "U1") (pin "6") (pinfunction "IO34_6") (pintype "input+no_connect"))
    )
    (net (code "65") (name "unconnected-(U1-IO35-Pad7)") (class "Default")
      (node (ref "U1") (pin "7") (pinfunction "IO35_7") (pintype "input+no_connect"))
    )
    (net (code "66") (name "unconnected-(U1-NC-Pad17)") (class "Default")
      (node (ref "U1") (pin "17") (pinfunction "NC_17") (pintype "input+no_connect"))
    )
    (net (code "67") (name "unconnected-(U1-NC-Pad18)") (class "Default")
      (node (ref "U1") (pin "18") (pinfunction "NC_18") (pintype "input+no_connect"))
    )
    (net (code "68") (name "unconnected-(U1-NC-Pad19)") (class "Default")
      (node (ref "U1") (pin "19") (pinfunction "NC_19") (pintype "input+no_connect"))
    )
    (net (code "69") (name "unconnected-(U1-NC-Pad20)") (class "Default")
      (node (ref "U1") (pin "20") (pinfunction "NC_20") (pintype "input+no_connect"))
    )
    (net (code "70") (name "unconnected-(U1-NC-Pad21)") (class "Default")
      (node (ref "U1") (pin "21") (pinfunction "NC_21") (pintype "input+no_connect"))
    )
    (net (code "71") (name "unconnected-(U1-NC-Pad22)") (class "Default")
      (node (ref "U1") (pin "22") (pinfunction "NC_22") (pintype "input+no_connect"))
    )
    (net (code "72") (name "unconnected-(U1-NC-Pad32)") (class "Default")
      (node (ref "U1") (pin "32") (pinfunction "NC_32") (pintype "input+no_connect"))
    )
    (net (code "73") (name "unconnected-(U1-SENSOR_VN-Pad5)") (class "Default")
      (node (ref "U1") (pin "5") (pinfunction "SENSOR_VN_5") (pintype "input+no_connect"))
    )
    (net (code "74") (name "unconnected-(U1-SENSOR_VP-Pad4)") (class "Default")
      (node (ref "U1") (pin "4") (pinfunction "SENSOR_VP_4") (pintype "input+no_connect"))
    )
    (net (code "75") (name "unconnected-(U2-CTS#-Pad9)") (class "Default")
      (node (ref "U2") (pin "9") (pinfunction "CTS#_9") (pintype "input+no_connect"))
    )
    (net (code "76") (name "unconnected-(U2-DCD#-Pad12)") (class "Default")
      (node (ref "U2") (pin "12") (pinfunction "DCD#_12") (pintype "input+no_connect"))
    )
    (net (code "77") (name "unconnected-(U2-DSR#-Pad10)") (class "Default")
      (node (ref "U2") (pin "10") (pinfunction "DSR#_10") (pintype "input+no_connect"))
    )
    (net (code "78") (name "unconnected-(U2-R232-Pad15)") (class "Default")
      (node (ref "U2") (pin "15") (pinfunction "R232_15") (pintype "input+no_connect"))
    )
    (net (code "79") (name "unconnected-(U2-RI#-Pad11)") (class "Default")
      (node (ref "U2") (pin "11") (pinfunction "RI#_11") (pintype "input+no_connect"))
    )
    (net (code "80") (name "unconnected-(U4-Pad3)") (class "Default")
      (node (ref "U4") (pin "3") (pinfunction "3_3") (pintype "input"))
    )
    (net (code "81") (name "unconnected-(U5-Pad3)") (class "Default")
      (node (ref "U5") (pin "3") (pinfunction "3_3") (pintype "input"))
    )
    (net (code "82") (name "unconnected-(U9-Pad3)") (class "Default")
      (node (ref "U9") (pin "3") (pinfunction "3_3") (pintype "input"))
    )
    (net (code "83") (name "unconnected-(U10-Pad3)") (class "Default")
      (node (ref "U10") (pin "3") (pinfunction "3_3") (pintype "input"))
    )
    (net (code "84") (name "unconnected-(U14-Pad3)") (class "Default")
      (node (ref "U14") (pin "3") (pinfunction "3_3") (pintype "input"))
    )
    (net (code "85") (name "unconnected-(U15-Pad3)") (class "Default")
      (node (ref "U15") (pin "3") (pinfunction "3_3") (pintype "input"))
    )
    (net (code "86") (name "unconnected-(USBC1-SBU1-PadA8)") (class "Default")
      (node (ref "USBC1") (pin "A8") (pinfunction "SBU1_A8") (pintype "input+no_connect"))
    )
    (net (code "87") (name "unconnected-(USBC1-SBU2-PadB8)") (class "Default")
      (node (ref "USBC1") (pin "B8") (pinfunction "SBU2_B8") (pintype "input+no_connect"))
    )
  )
)
